# Led_RGB.net
KiCad netlist of a schematic drawn in Altium Designer
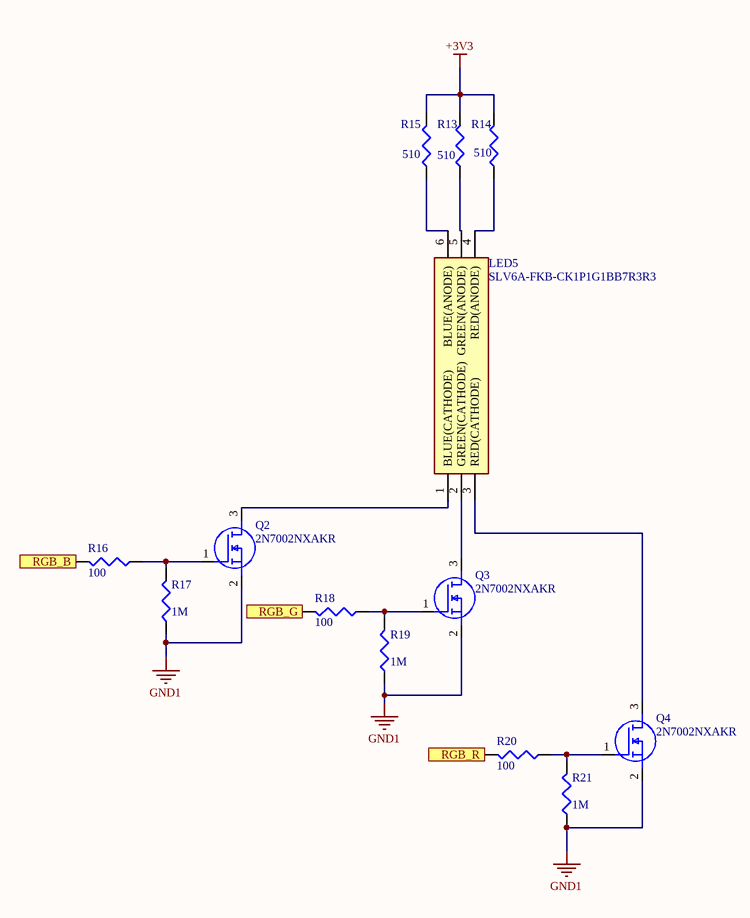
[diagram p0: Led RGB.SchDoc]

(export (version "E")
  (design (tool "Eeschema 10.0.6"))
  (components
    (comp (ref "LED5")
      (value "SLV6A-FKB-CK1P1G1BB7R3R3")
      (footprint "SamacSys:SLV6AFKBCKNPRGJBB7A363")
      (description "LED")
      (fields (field (name "MOUSER PART NUMBER") "941-S6AFKBCK1P1G17R3"))
      (libsource (lib "SamacSys") (part "SLV6A-FKB-CK1P1G1BB7R3R3"))
    )
    (comp (ref "Q2")
      (value "2N7002NXAKR")
      (footprint "SamacSys:SOT95P230X110-3N")
      (description "MOSFET (N-Channel)")
      (fields (field (name "MOUSER PART NUMBER") "771-2N7002NXAKR"))
      (libsource (lib "SamacSys") (part "2N7002NXAKR"))
    )
    (comp (ref "Q3")
      (value "2N7002NXAKR")
      (footprint "SamacSys:SOT95P230X110-3N")
      (description "MOSFET (N-Channel)")
      (fields (field (name "MOUSER PART NUMBER") "771-2N7002NXAKR"))
      (libsource (lib "SamacSys") (part "2N7002NXAKR"))
    )
    (comp (ref "Q4")
      (value "2N7002NXAKR")
      (footprint "SamacSys:SOT95P230X110-3N")
      (description "MOSFET (N-Channel)")
      (fields (field (name "MOUSER PART NUMBER") "771-2N7002NXAKR"))
      (libsource (lib "SamacSys") (part "2N7002NXAKR"))
    )
    (comp (ref "R13")
      (value "510")
      (footprint "J1-0603")
      (description "Resistor")
      (fields (field (name "Comment") "Res3") (field (name "PUBLISHER") "Altium Limited"))
      (libsource (lib "Miscellaneous Devices") (part "Res3"))
    )
    (comp (ref "R14")
      (value "510")
      (footprint "J1-0603")
      (description "Resistor")
      (fields (field (name "Comment") "Res3") (field (name "PUBLISHER") "Altium Limited"))
      (libsource (lib "Miscellaneous Devices") (part "Res3"))
    )
    (comp (ref "R15")
      (value "510")
      (footprint "J1-0603")
      (description "Resistor")
      (fields (field (name "Comment") "Res3") (field (name "PUBLISHER") "Altium Limited"))
      (libsource (lib "Miscellaneous Devices") (part "Res3"))
    )
    (comp (ref "R16")
      (value "100")
      (footprint "J1-0603")
      (description "Resistor")
      (fields (field (name "Comment") "Res3") (field (name "PUBLISHER") "Altium Limited"))
      (libsource (lib "Miscellaneous Devices") (part "Res3"))
    )
    (comp (ref "R17")
      (value "1M")
      (footprint "J1-0603")
      (description "Resistor")
      (fields (field (name "Comment") "Res3") (field (name "PUBLISHER") "Altium Limited"))
      (libsource (lib "Miscellaneous Devices") (part "Res3"))
    )
    (comp (ref "R18")
      (value "100")
      (footprint "J1-0603")
      (description "Resistor")
      (fields (field (name "Comment") "Res3") (field (name "PUBLISHER") "Altium Limited"))
      (libsource (lib "Miscellaneous Devices") (part "Res3"))
    )
    (comp (ref "R19")
      (value "1M")
      (footprint "J1-0603")
      (description "Resistor")
      (fields (field (name "Comment") "Res3") (field (name "PUBLISHER") "Altium Limited"))
      (libsource (lib "Miscellaneous Devices") (part "Res3"))
    )
    (comp (ref "R20")
      (value "100")
      (footprint "J1-0603")
      (description "Resistor")
      (fields (field (name "Comment") "Res3") (field (name "PUBLISHER") "Altium Limited"))
      (libsource (lib "Miscellaneous Devices") (part "Res3"))
    )
    (comp (ref "R21")
      (value "1M")
      (footprint "J1-0603")
      (description "Resistor")
      (fields (field (name "Comment") "Res3") (field (name "PUBLISHER") "Altium Limited"))
      (libsource (lib "Miscellaneous Devices") (part "Res3"))
    )
  )
  (nets
    (net (code "1") (name "+3V3") (class "Default")
      (node (ref "R13") (pin "2") (pinfunction "2_2") (pintype "passive"))
      (node (ref "R14") (pin "2") (pinfunction "2_2") (pintype "passive"))
      (node (ref "R15") (pin "2") (pinfunction "2_2") (pintype "passive"))
    )
    (net (code "2") (name "/RGB_B") (class "Default")
      (node (ref "R16") (pin "2") (pinfunction "2_2") (pintype "passive"))
    )
    (net (code "3") (name "/RGB_G") (class "Default")
      (node (ref "R18") (pin "2") (pinfunction "2_2") (pintype "passive"))
    )
    (net (code "4") (name "/RGB_R") (class "Default")
      (node (ref "R20") (pin "2") (pinfunction "2_2") (pintype "passive"))
    )
    (net (code "5") (name "GND1") (class "Default")
      (node (ref "Q2") (pin "2") (pinfunction "S_2") (pintype "passive"))
      (node (ref "Q3") (pin "2") (pinfunction "S_2") (pintype "passive"))
      (node (ref "Q4") (pin "2") (pinfunction "S_2") (pintype "passive"))
      (node (ref "R17") (pin "1") (pinfunction "1_1") (pintype "passive"))
      (node (ref "R19") (pin "1") (pinfunction "1_1") (pintype "passive"))
      (node (ref "R21") (pin "1") (pinfunction "1_1") (pintype "passive"))
    )
    (net (code "6") (name "Net-(LED5-BLUE(ANODE))") (class "Default")
      (node (ref "LED5") (pin "6") (pinfunction "BLUE(ANODE)_6") (pintype "passive"))
      (node (ref "R15") (pin "1") (pinfunction "1_1") (pintype "passive"))
    )
    (net (code "7") (name "Net-(LED5-BLUE(CATHODE))") (class "Default")
      (node (ref "LED5") (pin "1") (pinfunction "BLUE(CATHODE)_1") (pintype "passive"))
      (node (ref "Q2") (pin "3") (pinfunction "D_3") (pintype "passive"))
    )
    (net (code "8") (name "Net-(LED5-GREEN(ANODE))") (class "Default")
      (node (ref "LED5") (pin "5") (pinfunction "GREEN(ANODE)_5") (pintype "passive"))
      (node (ref "R13") (pin "1") (pinfunction "1_1") (pintype "passive"))
    )
    (net (code "9") (name "Net-(LED5-GREEN(CATHODE))") (class "Default")
      (node (ref "LED5") (pin "2") (pinfunction "GREEN(CATHODE)_2") (pintype "passive"))
      (node (ref "Q3") (pin "3") (pinfunction "D_3") (pintype "passive"))
    )
    (net (code "10") (name "Net-(LED5-RED(ANODE))") (class "Default")
      (node (ref "LED5") (pin "4") (pinfunction "RED(ANODE)_4") (pintype "passive"))
      (node (ref "R14") (pin "1") (pinfunction "1_1") (pintype "passive"))
    )
    (net (code "11") (name "Net-(LED5-RED(CATHODE))") (class "Default")
      (node (ref "LED5") (pin "3") (pinfunction "RED(CATHODE)_3") (pintype "passive"))
      (node (ref "Q4") (pin "3") (pinfunction "D_3") (pintype "passive"))
    )
    (net (code "12") (name "Net-(Q2-G)") (class "Default")
      (node (ref "Q2") (pin "1") (pinfunction "G_1") (pintype "passive"))
      (node (ref "R16") (pin "1") (pinfunction "1_1") (pintype "passive"))
      (node (ref "R17") (pin "2") (pinfunction "2_2") (pintype "passive"))
    )
    (net (code "13") (name "Net-(Q3-G)") (class "Default")
      (node (ref "Q3") (pin "1") (pinfunction "G_1") (pintype "passive"))
      (node (ref "R18") (pin "1") (pinfunction "1_1") (pintype "passive"))
      (node (ref "R19") (pin "2") (pinfunction "2_2") (pintype "passive"))
    )
    (net (code "14") (name "Net-(Q4-G)") (class "Default")
      (node (ref "Q4") (pin "1") (pinfunction "G_1") (pintype "passive"))
      (node (ref "R20") (pin "1") (pinfunction "1_1") (pintype "passive"))
      (node (ref "R21") (pin "2") (pinfunction "2_2") (pintype "passive"))
    )
  )
)
